# injection-feedforward.net
KiCad netlist of a schematic drawn in EAGLE
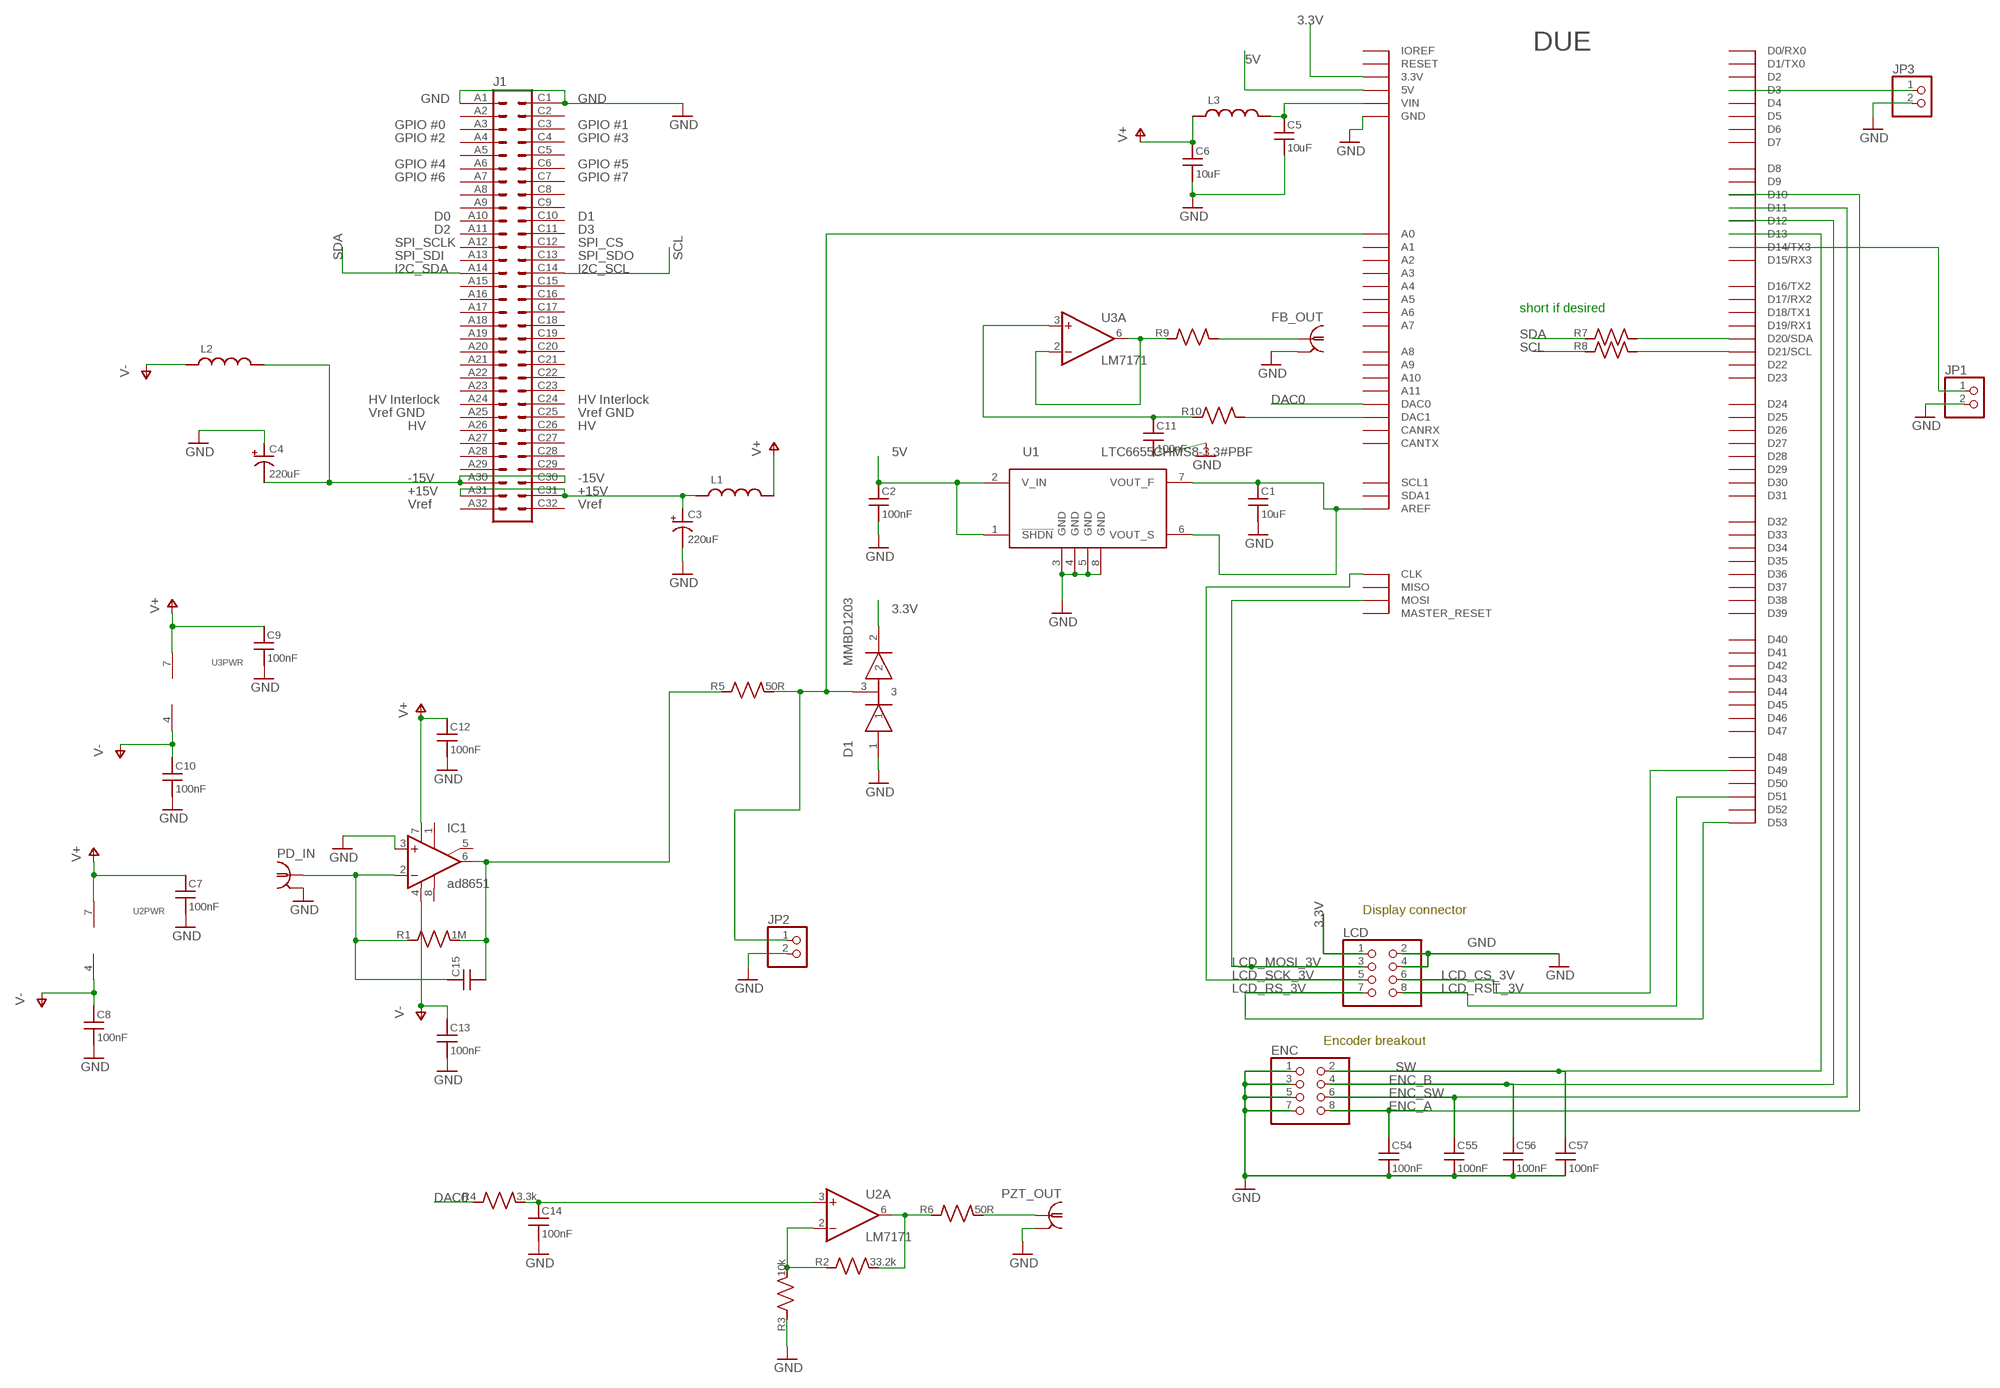
[diagram p0: schematic, sheet 1]

(export (version "E")
  (design (tool "Eeschema 10.0.6"))
  (components
    (comp (ref "C1")
      (value "10uF")
      (footprint "eagle-import:C_MLCC_0805")
      (libsource (lib "eagle-import") (part "C_MLCC_SMDCMLCC_0805"))
    )
    (comp (ref "C2")
      (value "100nF")
      (footprint "eagle-import:C_MLCC_0603")
      (libsource (lib "eagle-import") (part "C_MLCC_SMDCMLCC_0603"))
    )
    (comp (ref "C3")
      (value "220uF")
      (footprint "eagle-import:PANASONIC_F")
      (libsource (lib "eagle-import") (part "C_POL_SMDF"))
    )
    (comp (ref "C4")
      (value "220uF")
      (footprint "eagle-import:PANASONIC_F")
      (libsource (lib "eagle-import") (part "C_POL_SMDF"))
    )
    (comp (ref "C5")
      (value "10uF")
      (footprint "eagle-import:C_MLCC_0805")
      (libsource (lib "eagle-import") (part "C_MLCC_SMDCMLCC_0805"))
    )
    (comp (ref "C6")
      (value "10uF")
      (footprint "eagle-import:C_MLCC_0805")
      (libsource (lib "eagle-import") (part "C_MLCC_SMDCMLCC_0805"))
    )
    (comp (ref "C7")
      (value "100nF")
      (footprint "eagle-import:C_MLCC_0603")
      (libsource (lib "eagle-import") (part "C_MLCC_SMDCMLCC_0603"))
    )
    (comp (ref "C8")
      (value "100nF")
      (footprint "eagle-import:C_MLCC_0603")
      (libsource (lib "eagle-import") (part "C_MLCC_SMDCMLCC_0603"))
    )
    (comp (ref "C9")
      (value "100nF")
      (footprint "eagle-import:C_MLCC_0603")
      (libsource (lib "eagle-import") (part "C_MLCC_SMDCMLCC_0603"))
    )
    (comp (ref "C10")
      (value "100nF")
      (footprint "eagle-import:C_MLCC_0603")
      (libsource (lib "eagle-import") (part "C_MLCC_SMDCMLCC_0603"))
    )
    (comp (ref "C11")
      (value "100nF")
      (footprint "eagle-import:C_MLCC_0603")
      (libsource (lib "eagle-import") (part "C_MLCC_SMDCMLCC_0603"))
    )
    (comp (ref "C12")
      (value "100nF")
      (footprint "eagle-import:C_MLCC_0603")
      (libsource (lib "eagle-import") (part "C_MLCC_SMDCMLCC_0603"))
    )
    (comp (ref "C13")
      (value "100nF")
      (footprint "eagle-import:C_MLCC_0603")
      (libsource (lib "eagle-import") (part "C_MLCC_SMDCMLCC_0603"))
    )
    (comp (ref "C14")
      (value "100nF")
      (footprint "eagle-import:C_MLCC_0603")
      (libsource (lib "eagle-import") (part "C_MLCC_SMDCMLCC_0603"))
    )
    (comp (ref "C15")
      (value "C_MLCC_SMDCMLCC_0603")
      (footprint "eagle-import:C_MLCC_0603")
      (libsource (lib "eagle-import") (part "C_MLCC_SMDCMLCC_0603"))
    )
    (comp (ref "C54")
      (value "100nF")
      (footprint "eagle-import:C_MLCC_0603")
      (fields (field (name "PARTNO") "1276-1936-1-ND"))
      (libsource (lib "eagle-import") (part "C_MLCC_SMDCMLCC_0603"))
    )
    (comp (ref "C55")
      (value "100nF")
      (footprint "eagle-import:C_MLCC_0603")
      (fields (field (name "PARTNO") "1276-1936-1-ND"))
      (libsource (lib "eagle-import") (part "C_MLCC_SMDCMLCC_0603"))
    )
    (comp (ref "C56")
      (value "100nF")
      (footprint "eagle-import:C_MLCC_0603")
      (fields (field (name "PARTNO") "1276-1936-1-ND"))
      (libsource (lib "eagle-import") (part "C_MLCC_SMDCMLCC_0603"))
    )
    (comp (ref "C57")
      (value "100nF")
      (footprint "eagle-import:C_MLCC_0603")
      (fields (field (name "PARTNO") "1276-1936-1-ND"))
      (libsource (lib "eagle-import") (part "C_MLCC_SMDCMLCC_0603"))
    )
    (comp (ref "D1")
      (value "MMBD1203")
      (footprint "eagle-import:SOT23")
      (libsource (lib "eagle-import") (part "MMBD1203"))
    )
    (comp (ref "ENC")
      (value "PINHD-2X4-SHROUD")
      (footprint "eagle-import:ML08")
      (fields (field (name "PARTNO") "609-3530-ND"))
      (libsource (lib "eagle-import") (part "PINHD-2X4-SHROUD"))
    )
    (comp (ref "FB_OUT")
      (value "BNC-H")
      (footprint "eagle-import:BNC90")
      (libsource (lib "eagle-import") (part "BNC-H"))
    )
    (comp (ref "IC1")
      (value "ad8651")
      (footprint "eagle-import:SO08")
      (libsource (lib "eagle-import") (part "OPAMP-SO"))
    )
    (comp (ref "J1")
      (value "VG64C")
      (footprint "eagle-import:VG64-CUTOUT")
      (libsource (lib "eagle-import") (part "VG64C"))
    )
    (comp (ref "JP1")
      (value "PINHD-1X2")
      (footprint "eagle-import:1X02")
      (libsource (lib "eagle-import") (part "PINHD-1X2"))
    )
    (comp (ref "JP2")
      (value "PINHD-1X2")
      (footprint "eagle-import:1X02")
      (libsource (lib "eagle-import") (part "PINHD-1X2"))
    )
    (comp (ref "JP3")
      (value "PINHD-1X2")
      (footprint "eagle-import:1X02")
      (libsource (lib "eagle-import") (part "PINHD-1X2"))
    )
    (comp (ref "L1")
      (value "L_FERRITE_SMDLFERRITE_0603")
      (footprint "eagle-import:L_FERRITE_0603")
      (libsource (lib "eagle-import") (part "L_FERRITE_SMDLFERRITE_0603"))
    )
    (comp (ref "L2")
      (value "L_FERRITE_SMDLFERRITE_0603")
      (footprint "eagle-import:L_FERRITE_0603")
      (libsource (lib "eagle-import") (part "L_FERRITE_SMDLFERRITE_0603"))
    )
    (comp (ref "L3")
      (value "L_FERRITE_SMDLFERRITE_0603")
      (footprint "eagle-import:L_FERRITE_0603")
      (libsource (lib "eagle-import") (part "L_FERRITE_SMDLFERRITE_0603"))
    )
    (comp (ref "LCD")
      (value "PINHD-2X4-SHROUD")
      (footprint "eagle-import:ML08")
      (fields (field (name "PARTNO") "609-3530-ND"))
      (libsource (lib "eagle-import") (part "PINHD-2X4-SHROUD"))
    )
    (comp (ref "PD_IN")
      (value "BNC-H")
      (footprint "eagle-import:BNC90")
      (libsource (lib "eagle-import") (part "BNC-H"))
    )
    (comp (ref "PZT_OUT")
      (value "BNC-H")
      (footprint "eagle-import:BNC90")
      (libsource (lib "eagle-import") (part "BNC-H"))
    )
    (comp (ref "R1")
      (value "1M")
      (footprint "eagle-import:R_0603")
      (libsource (lib "eagle-import") (part "R_SMDR0603"))
    )
    (comp (ref "R2")
      (value "33.2k")
      (footprint "eagle-import:R_0603")
      (libsource (lib "eagle-import") (part "R_SMDR0603"))
    )
    (comp (ref "R3")
      (value "10k")
      (footprint "eagle-import:R_0603")
      (libsource (lib "eagle-import") (part "R_SMDR0603"))
    )
    (comp (ref "R4")
      (value "3.3k")
      (footprint "eagle-import:R_0603")
      (libsource (lib "eagle-import") (part "R_SMDR0603"))
    )
    (comp (ref "R5")
      (value "50R")
      (footprint "eagle-import:R_0603")
      (libsource (lib "eagle-import") (part "R_SMDR0603"))
    )
    (comp (ref "R6")
      (value "50R")
      (footprint "eagle-import:R_0603")
      (libsource (lib "eagle-import") (part "R_SMDR0603"))
    )
    (comp (ref "R7")
      (value "R_SMDR0603")
      (footprint "eagle-import:R_0603")
      (libsource (lib "eagle-import") (part "R_SMDR0603"))
    )
    (comp (ref "R8")
      (value "R_SMDR0603")
      (footprint "eagle-import:R_0603")
      (libsource (lib "eagle-import") (part "R_SMDR0603"))
    )
    (comp (ref "R9")
      (value "R_SMDR0603")
      (footprint "eagle-import:R_0603")
      (libsource (lib "eagle-import") (part "R_SMDR0603"))
    )
    (comp (ref "R10")
      (value "R_SMDR0603")
      (footprint "eagle-import:R_0603")
      (libsource (lib "eagle-import") (part "R_SMDR0603"))
    )
    (comp (ref "U$1")
      (value "DUE_SHIELD")
      (footprint "eagle-import:DUE_SHIELD")
      (libsource (lib "eagle-import") (part "DUE_SHIELD"))
    )
    (comp (ref "U1")
      (value "LTC6655CHMS8-3.3#PBF")
      (footprint "eagle-import:MSOP8")
      (libsource (lib "eagle-import") (part "LTC6655CHMS8-3.3#PBF"))
    )
    (comp (ref "U2")
      (value "LM7171")
      (footprint "eagle-import:SO08$1")
      (libsource (lib "eagle-import") (part "LM7171"))
    )
    (comp (ref "U3")
      (value "LM7171")
      (footprint "eagle-import:SO08$1")
      (libsource (lib "eagle-import") (part "LM7171"))
    )
  )
  (nets
    (net (code "1") (name "/3.3V") (class "Default")
      (node (ref "D1") (pin "2") (pinfunction "2_2") (pintype "bidirectional"))
      (node (ref "LCD") (pin "1") (pinfunction "1_1") (pintype "passive"))
      (node (ref "U$1") (pin "3.3") (pinfunction "3.3V_3.3") (pintype "bidirectional"))
    )
    (net (code "2") (name "/5V") (class "Default")
      (node (ref "C2") (pin "P$1") (pinfunction "1_P$1") (pintype "passive"))
      (node (ref "U$1") (pin "5V0") (pinfunction "5V_5V0") (pintype "bidirectional"))
      (node (ref "U$1") (pin "5V1") (pinfunction "5V_5V1") (pintype "bidirectional"))
      (node (ref "U$1") (pin "5V2") (pinfunction "5V_5V2") (pintype "bidirectional"))
      (node (ref "U$1") (pin "5V3") (pinfunction "5V_5V3") (pintype "bidirectional"))
      (node (ref "U1") (pin "1") (pinfunction "~{SHDN}_1") (pintype "bidirectional"))
      (node (ref "U1") (pin "2") (pinfunction "V_IN_2") (pintype "bidirectional"))
    )
    (net (code "3") (name "/DAC0") (class "Default")
      (node (ref "R4") (pin "P$1") (pinfunction "1_P$1") (pintype "passive"))
      (node (ref "U$1") (pin "DAC0") (pinfunction "DAC0_DAC0") (pintype "bidirectional"))
    )
    (net (code "4") (name "/ENC_A") (class "Default")
      (node (ref "C54") (pin "P$1") (pinfunction "1_P$1") (pintype "passive"))
      (node (ref "ENC") (pin "8") (pinfunction "8_8") (pintype "passive"))
      (node (ref "U$1") (pin "10") (pinfunction "D10_10") (pintype "bidirectional"))
    )
    (net (code "5") (name "/ENC_B") (class "Default")
      (node (ref "C56") (pin "P$1") (pinfunction "1_P$1") (pintype "passive"))
      (node (ref "ENC") (pin "4") (pinfunction "4_4") (pintype "passive"))
      (node (ref "U$1") (pin "12") (pinfunction "D12_12") (pintype "bidirectional"))
    )
    (net (code "6") (name "/ENC_SW") (class "Default")
      (node (ref "C55") (pin "P$1") (pinfunction "1_P$1") (pintype "passive"))
      (node (ref "ENC") (pin "6") (pinfunction "6_6") (pintype "passive"))
      (node (ref "U$1") (pin "11") (pinfunction "D11_11") (pintype "bidirectional"))
    )
    (net (code "7") (name "/LCD_CS_3V") (class "Default")
      (node (ref "LCD") (pin "6") (pinfunction "6_6") (pintype "passive"))
      (node (ref "U$1") (pin "49") (pinfunction "D49_49") (pintype "bidirectional"))
    )
    (net (code "8") (name "/LCD_MOSI_3V") (class "Default")
      (node (ref "LCD") (pin "3") (pinfunction "3_3") (pintype "passive"))
      (node (ref "U$1") (pin "MOSI") (pinfunction "MOSI_MOSI") (pintype "bidirectional"))
    )
    (net (code "9") (name "/LCD_RST_3V") (class "Default")
      (node (ref "LCD") (pin "8") (pinfunction "8_8") (pintype "passive"))
      (node (ref "U$1") (pin "51") (pinfunction "D51_51") (pintype "bidirectional"))
    )
    (net (code "10") (name "/LCD_RS_3V") (class "Default")
      (node (ref "LCD") (pin "7") (pinfunction "7_7") (pintype "passive"))
      (node (ref "U$1") (pin "53") (pinfunction "D53_53") (pintype "bidirectional"))
    )
    (net (code "11") (name "/LCD_SCK_3V") (class "Default")
      (node (ref "LCD") (pin "5") (pinfunction "5_5") (pintype "passive"))
      (node (ref "U$1") (pin "CLK") (pinfunction "CLK_CLK") (pintype "bidirectional"))
    )
    (net (code "12") (name "/SCL") (class "Default")
      (node (ref "J1") (pin "C14") (pinfunction "C14_C14") (pintype "passive"))
      (node (ref "R8") (pin "P$1") (pinfunction "1_P$1") (pintype "passive"))
    )
    (net (code "13") (name "/SDA") (class "Default")
      (node (ref "J1") (pin "A14") (pinfunction "A14_A14") (pintype "passive"))
      (node (ref "R7") (pin "P$1") (pinfunction "1_P$1") (pintype "passive"))
    )
    (net (code "14") (name "/SW") (class "Default")
      (node (ref "C57") (pin "P$1") (pinfunction "1_P$1") (pintype "passive"))
      (node (ref "ENC") (pin "2") (pinfunction "2_2") (pintype "passive"))
      (node (ref "U$1") (pin "13") (pinfunction "D13_13") (pintype "bidirectional"))
    )
    (net (code "15") (name "GND") (class "Default")
      (node (ref "C1") (pin "P$2") (pinfunction "2_P$2") (pintype "passive"))
      (node (ref "C10") (pin "P$2") (pinfunction "2_P$2") (pintype "passive"))
      (node (ref "C11") (pin "P$2") (pinfunction "2_P$2") (pintype "passive"))
      (node (ref "C12") (pin "P$2") (pinfunction "2_P$2") (pintype "passive"))
      (node (ref "C13") (pin "P$2") (pinfunction "2_P$2") (pintype "passive"))
      (node (ref "C14") (pin "P$2") (pinfunction "2_P$2") (pintype "passive"))
      (node (ref "C2") (pin "P$2") (pinfunction "2_P$2") (pintype "passive"))
      (node (ref "C3") (pin "-") (pinfunction "-_-") (pintype "passive"))
      (node (ref "C4") (pin "+") (pinfunction "+_+") (pintype "passive"))
      (node (ref "C5") (pin "P$2") (pinfunction "2_P$2") (pintype "passive"))
      (node (ref "C54") (pin "P$2") (pinfunction "2_P$2") (pintype "passive"))
      (node (ref "C55") (pin "P$2") (pinfunction "2_P$2") (pintype "passive"))
      (node (ref "C56") (pin "P$2") (pinfunction "2_P$2") (pintype "passive"))
      (node (ref "C57") (pin "P$2") (pinfunction "2_P$2") (pintype "passive"))
      (node (ref "C6") (pin "P$2") (pinfunction "2_P$2") (pintype "passive"))
      (node (ref "C7") (pin "P$2") (pinfunction "2_P$2") (pintype "passive"))
      (node (ref "C8") (pin "P$2") (pinfunction "2_P$2") (pintype "passive"))
      (node (ref "C9") (pin "P$2") (pinfunction "2_P$2") (pintype "passive"))
      (node (ref "D1") (pin "1") (pinfunction "1_1") (pintype "bidirectional"))
      (node (ref "ENC") (pin "1") (pinfunction "1_1") (pintype "passive"))
      (node (ref "ENC") (pin "3") (pinfunction "3_3") (pintype "passive"))
      (node (ref "ENC") (pin "5") (pinfunction "5_5") (pintype "passive"))
      (node (ref "ENC") (pin "7") (pinfunction "7_7") (pintype "passive"))
      (node (ref "FB_OUT") (pin "2") (pinfunction "2_2") (pintype "passive"))
      (node (ref "IC1") (pin "3") (pinfunction "+IN_3") (pintype "input"))
      (node (ref "J1") (pin "A1") (pinfunction "A1_A1") (pintype "passive"))
      (node (ref "J1") (pin "C1") (pinfunction "C1_C1") (pintype "passive"))
      (node (ref "JP1") (pin "2") (pinfunction "2_2") (pintype "passive"))
      (node (ref "JP2") (pin "2") (pinfunction "2_2") (pintype "passive"))
      (node (ref "JP3") (pin "2") (pinfunction "2_2") (pintype "passive"))
      (node (ref "LCD") (pin "2") (pinfunction "2_2") (pintype "passive"))
      (node (ref "LCD") (pin "4") (pinfunction "4_4") (pintype "passive"))
      (node (ref "PD_IN") (pin "2") (pinfunction "2_2") (pintype "passive"))
      (node (ref "PZT_OUT") (pin "2") (pinfunction "2_2") (pintype "passive"))
      (node (ref "R3") (pin "P$1") (pinfunction "1_P$1") (pintype "passive"))
      (node (ref "U$1") (pin "GND") (pinfunction "GND_GND") (pintype "bidirectional"))
      (node (ref "U$1") (pin "GND0") (pinfunction "GND_GND0") (pintype "bidirectional"))
      (node (ref "U$1") (pin "GND1") (pinfunction "GND_GND1") (pintype "bidirectional"))
      (node (ref "U$1") (pin "GND2") (pinfunction "GND_GND2") (pintype "bidirectional"))
      (node (ref "U$1") (pin "GND3") (pinfunction "GND_GND3") (pintype "bidirectional"))
      (node (ref "U$1") (pin "GND4") (pinfunction "GND_GND4") (pintype "bidirectional"))
      (node (ref "U1") (pin "3") (pinfunction "GND_3") (pintype "bidirectional"))
      (node (ref "U1") (pin "4") (pinfunction "GND_4") (pintype "bidirectional"))
      (node (ref "U1") (pin "5") (pinfunction "GND_5") (pintype "bidirectional"))
      (node (ref "U1") (pin "8") (pinfunction "GND_8") (pintype "bidirectional"))
    )
    (net (code "16") (name "Net-(C1-1)") (class "Default")
      (node (ref "C1") (pin "P$1") (pinfunction "1_P$1") (pintype "passive"))
      (node (ref "U$1") (pin "AREF") (pinfunction "AREF_AREF") (pintype "bidirectional"))
      (node (ref "U1") (pin "6") (pinfunction "VOUT_S_6") (pintype "bidirectional"))
      (node (ref "U1") (pin "7") (pinfunction "VOUT_F_7") (pintype "bidirectional"))
    )
    (net (code "17") (name "Net-(C5-1)") (class "Default")
      (node (ref "C5") (pin "P$1") (pinfunction "1_P$1") (pintype "passive"))
      (node (ref "L3") (pin "P$2") (pinfunction "2_P$2") (pintype "passive"))
      (node (ref "U$1") (pin "VIN") (pinfunction "VIN_VIN") (pintype "bidirectional"))
    )
    (net (code "18") (name "Net-(C11-1)") (class "Default")
      (node (ref "C11") (pin "P$1") (pinfunction "1_P$1") (pintype "passive"))
      (node (ref "R10") (pin "P$1") (pinfunction "1_P$1") (pintype "passive"))
      (node (ref "U3") (pin "3") (pinfunction "+IN_3") (pintype "input"))
    )
    (net (code "19") (name "Net-(C14-1)") (class "Default")
      (node (ref "C14") (pin "P$1") (pinfunction "1_P$1") (pintype "passive"))
      (node (ref "R4") (pin "P$2") (pinfunction "2_P$2") (pintype "passive"))
      (node (ref "U2") (pin "3") (pinfunction "+IN_3") (pintype "input"))
    )
    (net (code "20") (name "Net-(C15-1)") (class "Default")
      (node (ref "C15") (pin "P$1") (pinfunction "1_P$1") (pintype "passive"))
      (node (ref "IC1") (pin "2") (pinfunction "-IN_2") (pintype "input"))
      (node (ref "PD_IN") (pin "1") (pinfunction "1_1") (pintype "passive"))
      (node (ref "R1") (pin "P$1") (pinfunction "1_P$1") (pintype "passive"))
    )
    (net (code "21") (name "Net-(C15-2)") (class "Default")
      (node (ref "C15") (pin "P$2") (pinfunction "2_P$2") (pintype "passive"))
      (node (ref "IC1") (pin "6") (pinfunction "OUT_6") (pintype "output"))
      (node (ref "R1") (pin "P$2") (pinfunction "2_P$2") (pintype "passive"))
      (node (ref "R5") (pin "P$1") (pinfunction "1_P$1") (pintype "passive"))
    )
    (net (code "22") (name "Net-(L1-1)") (class "Default")
      (node (ref "C3") (pin "+") (pinfunction "+_+") (pintype "passive"))
      (node (ref "J1") (pin "A31") (pinfunction "A31_A31") (pintype "passive"))
      (node (ref "J1") (pin "C31") (pinfunction "C31_C31") (pintype "passive"))
      (node (ref "L1") (pin "P$1") (pinfunction "1_P$1") (pintype "passive"))
    )
    (net (code "23") (name "Net-(L2-2)") (class "Default")
      (node (ref "C4") (pin "-") (pinfunction "-_-") (pintype "passive"))
      (node (ref "J1") (pin "A30") (pinfunction "A30_A30") (pintype "passive"))
      (node (ref "J1") (pin "C30") (pinfunction "C30_C30") (pintype "passive"))
      (node (ref "L2") (pin "P$2") (pinfunction "2_P$2") (pintype "passive"))
    )
    (net (code "24") (name "Net-(R2-1)") (class "Default")
      (node (ref "R2") (pin "P$1") (pinfunction "1_P$1") (pintype "passive"))
      (node (ref "R3") (pin "P$2") (pinfunction "2_P$2") (pintype "passive"))
      (node (ref "U2") (pin "2") (pinfunction "-IN_2") (pintype "input"))
    )
    (net (code "25") (name "Net-(R2-2)") (class "Default")
      (node (ref "R2") (pin "P$2") (pinfunction "2_P$2") (pintype "passive"))
      (node (ref "R6") (pin "P$1") (pinfunction "1_P$1") (pintype "passive"))
      (node (ref "U2") (pin "6") (pinfunction "OUT_6") (pintype "output"))
    )
    (net (code "26") (name "Net-(R5-2)") (class "Default")
      (node (ref "D1") (pin "3") (pinfunction "3_3") (pintype "bidirectional"))
      (node (ref "JP2") (pin "1") (pinfunction "1_1") (pintype "passive"))
      (node (ref "R5") (pin "P$2") (pinfunction "2_P$2") (pintype "passive"))
      (node (ref "U$1") (pin "A0") (pinfunction "A0_A0") (pintype "bidirectional"))
    )
    (net (code "27") (name "Net-(R6-2)") (class "Default")
      (node (ref "PZT_OUT") (pin "1") (pinfunction "1_1") (pintype "passive"))
      (node (ref "R6") (pin "P$2") (pinfunction "2_P$2") (pintype "passive"))
    )
    (net (code "28") (name "Net-(R7-2)") (class "Default")
      (node (ref "R7") (pin "P$2") (pinfunction "2_P$2") (pintype "passive"))
      (node (ref "U$1") (pin "20") (pinfunction "D20/SDA_20") (pintype "bidirectional"))
    )
    (net (code "29") (name "Net-(R8-2)") (class "Default")
      (node (ref "R8") (pin "P$2") (pinfunction "2_P$2") (pintype "passive"))
      (node (ref "U$1") (pin "21") (pinfunction "D21/SCL_21") (pintype "bidirectional"))
    )
    (net (code "30") (name "Net-(R9-1)") (class "Default")
      (node (ref "R9") (pin "P$1") (pinfunction "1_P$1") (pintype "passive"))
      (node (ref "U3") (pin "2") (pinfunction "-IN_2") (pintype "input"))
      (node (ref "U3") (pin "6") (pinfunction "OUT_6") (pintype "output"))
    )
    (net (code "31") (name "Net-(R9-2)") (class "Default")
      (node (ref "FB_OUT") (pin "1") (pinfunction "1_1") (pintype "passive"))
      (node (ref "R9") (pin "P$2") (pinfunction "2_P$2") (pintype "passive"))
    )
    (net (code "32") (name "Net-(R10-2)") (class "Default")
      (node (ref "R10") (pin "P$2") (pinfunction "2_P$2") (pintype "passive"))
      (node (ref "U$1") (pin "DAC1") (pinfunction "DAC1_DAC1") (pintype "bidirectional"))
    )
    (net (code "33") (name "Net-(U$1-D3)") (class "Default")
      (node (ref "JP3") (pin "1") (pinfunction "1_1") (pintype "passive"))
      (node (ref "U$1") (pin "3") (pinfunction "D3_3") (pintype "bidirectional"))
    )
    (net (code "34") (name "Net-(U$1-D14{slash}TX3)") (class "Default")
      (node (ref "JP1") (pin "1") (pinfunction "1_1") (pintype "passive"))
      (node (ref "U$1") (pin "14") (pinfunction "D14/TX3_14") (pintype "bidirectional"))
    )
    (net (code "35") (name "V+") (class "Default")
      (node (ref "C12") (pin "P$1") (pinfunction "1_P$1") (pintype "passive"))
      (node (ref "C6") (pin "P$1") (pinfunction "1_P$1") (pintype "passive"))
      (node (ref "C7") (pin "P$1") (pinfunction "1_P$1") (pintype "passive"))
      (node (ref "C9") (pin "P$1") (pinfunction "1_P$1") (pintype "passive"))
      (node (ref "IC1") (pin "7") (pinfunction "V+_7") (pintype "power_in"))
      (node (ref "L1") (pin "P$2") (pinfunction "2_P$2") (pintype "passive"))
      (node (ref "L3") (pin "P$1") (pinfunction "1_P$1") (pintype "passive"))
      (node (ref "U2") (pin "7") (pinfunction "V+_7") (pintype "power_in"))
      (node (ref "U3") (pin "7") (pinfunction "V+_7") (pintype "power_in"))
    )
    (net (code "36") (name "V-") (class "Default")
      (node (ref "C10") (pin "P$1") (pinfunction "1_P$1") (pintype "passive"))
      (node (ref "C13") (pin "P$1") (pinfunction "1_P$1") (pintype "passive"))
      (node (ref "C8") (pin "P$1") (pinfunction "1_P$1") (pintype "passive"))
      (node (ref "IC1") (pin "4") (pinfunction "V-_4") (pintype "power_in"))
      (node (ref "L2") (pin "P$1") (pinfunction "1_P$1") (pintype "passive"))
      (node (ref "U2") (pin "4") (pinfunction "V-_4") (pintype "power_in"))
      (node (ref "U3") (pin "4") (pinfunction "V-_4") (pintype "power_in"))
    )
    (net (code "37") (name "unconnected-(IC1-ON1-Pad1)") (class "Default")
      (node (ref "IC1") (pin "1") (pinfunction "ON1_1") (pintype "passive"))
    )
    (net (code "38") (name "unconnected-(IC1-ON2-Pad5)") (class "Default")
      (node (ref "IC1") (pin "5") (pinfunction "ON2_5") (pintype "passive"))
    )
    (net (code "39") (name "unconnected-(IC1-OPT-Pad8)") (class "Default")
      (node (ref "IC1") (pin "8") (pinfunction "OPT_8") (pintype "passive"))
    )
    (net (code "40") (name "unconnected-(J1-PadA2)") (class "Default")
      (node (ref "J1") (pin "A2") (pinfunction "A2_A2") (pintype "passive"))
    )
    (net (code "41") (name "unconnected-(J1-PadA3)") (class "Default")
      (node (ref "J1") (pin "A3") (pinfunction "A3_A3") (pintype "passive"))
    )
    (net (code "42") (name "unconnected-(J1-PadA4)") (class "Default")
      (node (ref "J1") (pin "A4") (pinfunction "A4_A4") (pintype "passive"))
    )
    (net (code "43") (name "unconnected-(J1-PadA5)") (class "Default")
      (node (ref "J1") (pin "A5") (pinfunction "A5_A5") (pintype "passive"))
    )
    (net (code "44") (name "unconnected-(J1-PadA6)") (class "Default")
      (node (ref "J1") (pin "A6") (pinfunction "A6_A6") (pintype "passive"))
    )
    (net (code "45") (name "unconnected-(J1-PadA7)") (class "Default")
      (node (ref "J1") (pin "A7") (pinfunction "A7_A7") (pintype "passive"))
    )
    (net (code "46") (name "unconnected-(J1-PadA8)") (class "Default")
      (node (ref "J1") (pin "A8") (pinfunction "A8_A8") (pintype "passive"))
    )
    (net (code "47") (name "unconnected-(J1-PadA9)") (class "Default")
      (node (ref "J1") (pin "A9") (pinfunction "A9_A9") (pintype "passive"))
    )
    (net (code "48") (name "unconnected-(J1-PadA10)") (class "Default")
      (node (ref "J1") (pin "A10") (pinfunction "A10_A10") (pintype "passive"))
    )
    (net (code "49") (name "unconnected-(J1-PadA11)") (class "Default")
      (node (ref "J1") (pin "A11") (pinfunction "A11_A11") (pintype "passive"))
    )
    (net (code "50") (name "unconnected-(J1-PadA12)") (class "Default")
      (node (ref "J1") (pin "A12") (pinfunction "A12_A12") (pintype "passive"))
    )
    (net (code "51") (name "unconnected-(J1-PadA13)") (class "Default")
      (node (ref "J1") (pin "A13") (pinfunction "A13_A13") (pintype "passive"))
    )
    (net (code "52") (name "unconnected-(J1-PadA15)") (class "Default")
      (node (ref "J1") (pin "A15") (pinfunction "A15_A15") (pintype "passive"))
    )
    (net (code "53") (name "unconnected-(J1-PadA16)") (class "Default")
      (node (ref "J1") (pin "A16") (pinfunction "A16_A16") (pintype "passive"))
    )
    (net (code "54") (name "unconnected-(J1-PadA17)") (class "Default")
      (node (ref "J1") (pin "A17") (pinfunction "A17_A17") (pintype "passive"))
    )
    (net (code "55") (name "unconnected-(J1-PadA18)") (class "Default")
      (node (ref "J1") (pin "A18") (pinfunction "A18_A18") (pintype "passive"))
    )
    (net (code "56") (name "unconnected-(J1-PadA19)") (class "Default")
      (node (ref "J1") (pin "A19") (pinfunction "A19_A19") (pintype "passive"))
    )
    (net (code "57") (name "unconnected-(J1-PadA20)") (class "Default")
      (node (ref "J1") (pin "A20") (pinfunction "A20_A20") (pintype "passive"))
    )
    (net (code "58") (name "unconnected-(J1-PadA21)") (class "Default")
      (node (ref "J1") (pin "A21") (pinfunction "A21_A21") (pintype "passive"))
    )
    (net (code "59") (name "unconnected-(J1-PadA22)") (class "Default")
      (node (ref "J1") (pin "A22") (pinfunction "A22_A22") (pintype "passive"))
    )
    (net (code "60") (name "unconnected-(J1-PadA23)") (class "Default")
      (node (ref "J1") (pin "A23") (pinfunction "A23_A23") (pintype "passive"))
    )
    (net (code "61") (name "unconnected-(J1-PadA24)") (class "Default")
      (node (ref "J1") (pin "A24") (pinfunction "A24_A24") (pintype "passive"))
    )
    (net (code "62") (name "unconnected-(J1-PadA25)") (class "Default")
      (node (ref "J1") (pin "A25") (pinfunction "A25_A25") (pintype "passive"))
    )
    (net (code "63") (name "unconnected-(J1-PadA26)") (class "Default")
      (node (ref "J1") (pin "A26") (pinfunction "A26_A26") (pintype "passive"))
    )
    (net (code "64") (name "unconnected-(J1-PadA27)") (class "Default")
      (node (ref "J1") (pin "A27") (pinfunction "A27_A27") (pintype "passive"))
    )
    (net (code "65") (name "unconnected-(J1-PadA28)") (class "Default")
      (node (ref "J1") (pin "A28") (pinfunction "A28_A28") (pintype "passive"))
    )
    (net (code "66") (name "unconnected-(J1-PadA29)") (class "Default")
      (node (ref "J1") (pin "A29") (pinfunction "A29_A29") (pintype "passive"))
    )
    (net (code "67") (name "unconnected-(J1-PadA32)") (class "Default")
      (node (ref "J1") (pin "A32") (pinfunction "A32_A32") (pintype "passive"))
    )
    (net (code "68") (name "unconnected-(J1-PadC2)") (class "Default")
      (node (ref "J1") (pin "C2") (pinfunction "C2_C2") (pintype "passive"))
    )
    (net (code "69") (name "unconnected-(J1-PadC3)") (class "Default")
      (node (ref "J1") (pin "C3") (pinfunction "C3_C3") (pintype "passive"))
    )
    (net (code "70") (name "unconnected-(J1-PadC4)") (class "Default")
      (node (ref "J1") (pin "C4") (pinfunction "C4_C4") (pintype "passive"))
    )
    (net (code "71") (name "unconnected-(J1-PadC5)") (class "Default")
      (node (ref "J1") (pin "C5") (pinfunction "C5_C5") (pintype "passive"))
    )
    (net (code "72") (name "unconnected-(J1-PadC6)") (class "Default")
      (node (ref "J1") (pin "C6") (pinfunction "C6_C6") (pintype "passive"))
    )
    (net (code "73") (name "unconnected-(J1-PadC7)") (class "Default")
      (node (ref "J1") (pin "C7") (pinfunction "C7_C7") (pintype "passive"))
    )
    (net (code "74") (name "unconnected-(J1-PadC8)") (class "Default")
      (node (ref "J1") (pin "C8") (pinfunction "C8_C8") (pintype "passive"))
    )
    (net (code "75") (name "unconnected-(J1-PadC9)") (class "Default")
      (node (ref "J1") (pin "C9") (pinfunction "C9_C9") (pintype "passive"))
    )
    (net (code "76") (name "unconnected-(J1-PadC10)") (class "Default")
      (node (ref "J1") (pin "C10") (pinfunction "C10_C10") (pintype "passive"))
    )
    (net (code "77") (name "unconnected-(J1-PadC11)") (class "Default")
      (node (ref "J1") (pin "C11") (pinfunction "C11_C11") (pintype "passive"))
    )
    (net (code "78") (name "unconnected-(J1-PadC12)") (class "Default")
      (node (ref "J1") (pin "C12") (pinfunction "C12_C12") (pintype "passive"))
    )
    (net (code "79") (name "unconnected-(J1-PadC13)") (class "Default")
      (node (ref "J1") (pin "C13") (pinfunction "C13_C13") (pintype "passive"))
    )
    (net (code "80") (name "unconnected-(J1-PadC15)") (class "Default")
      (node (ref "J1") (pin "C15") (pinfunction "C15_C15") (pintype "passive"))
    )
    (net (code "81") (name "unconnected-(J1-PadC16)") (class "Default")
      (node (ref "J1") (pin "C16") (pinfunction "C16_C16") (pintype "passive"))
    )
    (net (code "82") (name "unconnected-(J1-PadC17)") (class "Default")
      (node (ref "J1") (pin "C17") (pinfunction "C17_C17") (pintype "passive"))
    )
    (net (code "83") (name "unconnected-(J1-PadC18)") (class "Default")
      (node (ref "J1") (pin "C18") (pinfunction "C18_C18") (pintype "passive"))
    )
    (net (code "84") (name "unconnected-(J1-PadC19)") (class "Default")
      (node (ref "J1") (pin "C19") (pinfunction "C19_C19") (pintype "passive"))
    )
    (net (code "85") (name "unconnected-(J1-PadC20)") (class "Default")
      (node (ref "J1") (pin "C20") (pinfunction "C20_C20") (pintype "passive"))
    )
    (net (code "86") (name "unconnected-(J1-PadC21)") (class "Default")
      (node (ref "J1") (pin "C21") (pinfunction "C21_C21") (pintype "passive"))
    )
    (net (code "87") (name "unconnected-(J1-PadC22)") (class "Default")
      (node (ref "J1") (pin "C22") (pinfunction "C22_C22") (pintype "passive"))
    )
    (net (code "88") (name "unconnected-(J1-PadC23)") (class "Default")
      (node (ref "J1") (pin "C23") (pinfunction "C23_C23") (pintype "passive"))
    )
    (net (code "89") (name "unconnected-(J1-PadC24)") (class "Default")
      (node (ref "J1") (pin "C24") (pinfunction "C24_C24") (pintype "passive"))
    )
    (net (code "90") (name "unconnected-(J1-PadC25)") (class "Default")
      (node (ref "J1") (pin "C25") (pinfunction "C25_C25") (pintype "passive"))
    )
    (net (code "91") (name "unconnected-(J1-PadC26)") (class "Default")
      (node (ref "J1") (pin "C26") (pinfunction "C26_C26") (pintype "passive"))
    )
    (net (code "92") (name "unconnected-(J1-PadC27)") (class "Default")
      (node (ref "J1") (pin "C27") (pinfunction "C27_C27") (pintype "passive"))
    )
    (net (code "93") (name "unconnected-(J1-PadC28)") (class "Default")
      (node (ref "J1") (pin "C28") (pinfunction "C28_C28") (pintype "passive"))
    )
    (net (code "94") (name "unconnected-(J1-PadC29)") (class "Default")
      (node (ref "J1") (pin "C29") (pinfunction "C29_C29") (pintype "passive"))
    )
    (net (code "95") (name "unconnected-(J1-PadC32)") (class "Default")
      (node (ref "J1") (pin "C32") (pinfunction "C32_C32") (pintype "passive"))
    )
    (net (code "96") (name "unconnected-(U$1-D0{slash}RX0-Pad0)") (class "Default")
      (node (ref "U$1") (pin "0") (pinfunction "D0/RX0_0") (pintype "bidirectional"))
    )
    (net (code "97") (name "unconnected-(U$1-D1{slash}TX0-Pad1)") (class "Default")
      (node (ref "U$1") (pin "1") (pinfunction "D1/TX0_1") (pintype "bidirectional"))
    )
    (net (code "98") (name "unconnected-(U$1-D2-Pad2)") (class "Default")
      (node (ref "U$1") (pin "2") (pinfunction "D2_2") (pintype "bidirectional"))
    )
    (net (code "99") (name "unconnected-(U$1-D4-Pad4)") (class "Default")
      (node (ref "U$1") (pin "4") (pinfunction "D4_4") (pintype "bidirectional"))
    )
    (net (code "100") (name "unconnected-(U$1-D5-Pad5)") (class "Default")
      (node (ref "U$1") (pin "5") (pinfunction "D5_5") (pintype "bidirectional"))
    )
    (net (code "101") (name "unconnected-(U$1-D6-Pad6)") (class "Default")
      (node (ref "U$1") (pin "6") (pinfunction "D6_6") (pintype "bidirectional"))
    )
    (net (code "102") (name "unconnected-(U$1-D7-Pad7)") (class "Default")
      (node (ref "U$1") (pin "7") (pinfunction "D7_7") (pintype "bidirectional"))
    )
    (net (code "103") (name "unconnected-(U$1-D8-Pad8)") (class "Default")
      (node (ref "U$1") (pin "8") (pinfunction "D8_8") (pintype "bidirectional"))
    )
    (net (code "104") (name "unconnected-(U$1-D9-Pad9)") (class "Default")
      (node (ref "U$1") (pin "9") (pinfunction "D9_9") (pintype "bidirectional"))
    )
    (net (code "105") (name "unconnected-(U$1-D15{slash}RX3-Pad15)") (class "Default")
      (node (ref "U$1") (pin "15") (pinfunction "D15/RX3_15") (pintype "bidirectional"))
    )
    (net (code "106") (name "unconnected-(U$1-D16{slash}TX2-Pad16)") (class "Default")
      (node (ref "U$1") (pin "16") (pinfunction "D16/TX2_16") (pintype "bidirectional"))
    )
    (net (code "107") (name "unconnected-(U$1-D17{slash}RX2-Pad17)") (class "Default")
      (node (ref "U$1") (pin "17") (pinfunction "D17/RX2_17") (pintype "bidirectional"))
    )
    (net (code "108") (name "unconnected-(U$1-D18{slash}TX1-Pad18)") (class "Default")
      (node (ref "U$1") (pin "18") (pinfunction "D18/TX1_18") (pintype "bidirectional"))
    )
    (net (code "109") (name "unconnected-(U$1-D19{slash}RX1-Pad19)") (class "Default")
      (node (ref "U$1") (pin "19") (pinfunction "D19/RX1_19") (pintype "bidirectional"))
    )
    (net (code "110") (name "unconnected-(U$1-D22-Pad22)") (class "Default")
      (node (ref "U$1") (pin "22") (pinfunction "D22_22") (pintype "bidirectional"))
    )
    (net (code "111") (name "unconnected-(U$1-D23-Pad23)") (class "Default")
      (node (ref "U$1") (pin "23") (pinfunction "D23_23") (pintype "bidirectional"))
    )
    (net (code "112") (name "unconnected-(U$1-D24-Pad24)") (class "Default")
      (node (ref "U$1") (pin "24") (pinfunction "D24_24") (pintype "bidirectional"))
    )
    (net (code "113") (name "unconnected-(U$1-D25-Pad25)") (class "Default")
      (node (ref "U$1") (pin "25") (pinfunction "D25_25") (pintype "bidirectional"))
    )
    (net (code "114") (name "unconnected-(U$1-D26-Pad26)") (class "Default")
      (node (ref "U$1") (pin "26") (pinfunction "D26_26") (pintype "bidirectional"))
    )
    (net (code "115") (name "unconnected-(U$1-D27-Pad27)") (class "Default")
      (node (ref "U$1") (pin "27") (pinfunction "D27_27") (pintype "bidirectional"))
    )
    (net (code "116") (name "unconnected-(U$1-D28-Pad28)") (class "Default")
      (node (ref "U$1") (pin "28") (pinfunction "D28_28") (pintype "bidirectional"))
    )
    (net (code "117") (name "unconnected-(U$1-D29-Pad29)") (class "Default")
      (node (ref "U$1") (pin "29") (pinfunction "D29_29") (pintype "bidirectional"))
    )
    (net (code "118") (name "unconnected-(U$1-D30-Pad30)") (class "Default")
      (node (ref "U$1") (pin "30") (pinfunction "D30_30") (pintype "bidirectional"))
    )
    (net (code "119") (name "unconnected-(U$1-D31-Pad31)") (class "Default")
      (node (ref "U$1") (pin "31") (pinfunction "D31_31") (pintype "bidirectional"))
    )
    (net (code "120") (name "unconnected-(U$1-D32-Pad32)") (class "Default")
      (node (ref "U$1") (pin "32") (pinfunction "D32_32") (pintype "bidirectional"))
    )
    (net (code "121") (name "unconnected-(U$1-D33-Pad33)") (class "Default")
      (node (ref "U$1") (pin "33") (pinfunction "D33_33") (pintype "bidirectional"))
    )
    (net (code "122") (name "unconnected-(U$1-D34-Pad34)") (class "Default")
      (node (ref "U$1") (pin "34") (pinfunction "D34_34") (pintype "bidirectional"))
    )
    (net (code "123") (name "unconnected-(U$1-D35-Pad35)") (class "Default")
      (node (ref "U$1") (pin "35") (pinfunction "D35_35") (pintype "bidirectional"))
    )
    (net (code "124") (name "unconnected-(U$1-D36-Pad36)") (class "Default")
      (node (ref "U$1") (pin "36") (pinfunction "D36_36") (pintype "bidirectional"))
    )
    (net (code "125") (name "unconnected-(U$1-D37-Pad37)") (class "Default")
      (node (ref "U$1") (pin "37") (pinfunction "D37_37") (pintype "bidirectional"))
    )
    (net (code "126") (name "unconnected-(U$1-D38-Pad38)") (class "Default")
      (node (ref "U$1") (pin "38") (pinfunction "D38_38") (pintype "bidirectional"))
    )
    (net (code "127") (name "unconnected-(U$1-D39-Pad39)") (class "Default")
      (node (ref "U$1") (pin "39") (pinfunction "D39_39") (pintype "bidirectional"))
    )
    (net (code "128") (name "unconnected-(U$1-D40-Pad40)") (class "Default")
      (node (ref "U$1") (pin "40") (pinfunction "D40_40") (pintype "bidirectional"))
    )
    (net (code "129") (name "unconnected-(U$1-D41-Pad41)") (class "Default")
      (node (ref "U$1") (pin "41") (pinfunction "D41_41") (pintype "bidirectional"))
    )
    (net (code "130") (name "unconnected-(U$1-D42-Pad42)") (class "Default")
      (node (ref "U$1") (pin "42") (pinfunction "D42_42") (pintype "bidirectional"))
    )
    (net (code "131") (name "unconnected-(U$1-D43-Pad43)") (class "Default")
      (node (ref "U$1") (pin "43") (pinfunction "D43_43") (pintype "bidirectional"))
    )
    (net (code "132") (name "unconnected-(U$1-D44-Pad44)") (class "Default")
      (node (ref "U$1") (pin "44") (pinfunction "D44_44") (pintype "bidirectional"))
    )
    (net (code "133") (name "unconnected-(U$1-D45-Pad45)") (class "Default")
      (node (ref "U$1") (pin "45") (pinfunction "D45_45") (pintype "bidirectional"))
    )
    (net (code "134") (name "unconnected-(U$1-D46-Pad46)") (class "Default")
      (node (ref "U$1") (pin "46") (pinfunction "D46_46") (pintype "bidirectional"))
    )
    (net (code "135") (name "unconnected-(U$1-D47-Pad47)") (class "Default")
      (node (ref "U$1") (pin "47") (pinfunction "D47_47") (pintype "bidirectional"))
    )
    (net (code "136") (name "unconnected-(U$1-D48-Pad48)") (class "Default")
      (node (ref "U$1") (pin "48") (pinfunction "D48_48") (pintype "bidirectional"))
    )
    (net (code "137") (name "unconnected-(U$1-D50-Pad50)") (class "Default")
      (node (ref "U$1") (pin "50") (pinfunction "D50_50") (pintype "bidirectional"))
    )
    (net (code "138") (name "unconnected-(U$1-D52-Pad52)") (class "Default")
      (node (ref "U$1") (pin "52") (pinfunction "D52_52") (pintype "bidirectional"))
    )
    (net (code "139") (name "unconnected-(U$1-PadA1)") (class "Default")
      (node (ref "U$1") (pin "A1") (pinfunction "A1_A1") (pintype "bidirectional"))
    )
    (net (code "140") (name "unconnected-(U$1-PadA2)") (class "Default")
      (node (ref "U$1") (pin "A2") (pinfunction "A2_A2") (pintype "bidirectional"))
    )
    (net (code "141") (name "unconnected-(U$1-PadA3)") (class "Default")
      (node (ref "U$1") (pin "A3") (pinfunction "A3_A3") (pintype "bidirectional"))
    )
    (net (code "142") (name "unconnected-(U$1-PadA4)") (class "Default")
      (node (ref "U$1") (pin "A4") (pinfunction "A4_A4") (pintype "bidirectional"))
    )
    (net (code "143") (name "unconnected-(U$1-PadA5)") (class "Default")
      (node (ref "U$1") (pin "A5") (pinfunction "A5_A5") (pintype "bidirectional"))
    )
    (net (code "144") (name "unconnected-(U$1-PadA6)") (class "Default")
      (node (ref "U$1") (pin "A6") (pinfunction "A6_A6") (pintype "bidirectional"))
    )
    (net (code "145") (name "unconnected-(U$1-PadA7)") (class "Default")
      (node (ref "U$1") (pin "A7") (pinfunction "A7_A7") (pintype "bidirectional"))
    )
    (net (code "146") (name "unconnected-(U$1-PadA8)") (class "Default")
      (node (ref "U$1") (pin "A8") (pinfunction "A8_A8") (pintype "bidirectional"))
    )
    (net (code "147") (name "unconnected-(U$1-PadA9)") (class "Default")
      (node (ref "U$1") (pin "A9") (pinfunction "A9_A9") (pintype "bidirectional"))
    )
    (net (code "148") (name "unconnected-(U$1-PadA10)") (class "Default")
      (node (ref "U$1") (pin "A10") (pinfunction "A10_A10") (pintype "bidirectional"))
    )
    (net (code "149") (name "unconnected-(U$1-PadA11)") (class "Default")
      (node (ref "U$1") (pin "A11") (pinfunction "A11_A11") (pintype "bidirectional"))
    )
    (net (code "150") (name "unconnected-(U$1-PadCANRX)") (class "Default")
      (node (ref "U$1") (pin "CANRX") (pinfunction "CANRX_CANRX") (pintype "bidirectional"))
    )
    (net (code "151") (name "unconnected-(U$1-PadCANTX)") (class "Default")
      (node (ref "U$1") (pin "CANTX") (pinfunction "CANTX_CANTX") (pintype "bidirectional"))
    )
    (net (code "152") (name "unconnected-(U$1-PadIOREF)") (class "Default")
      (node (ref "U$1") (pin "IOREF") (pinfunction "IOREF_IOREF") (pintype "bidirectional"))
    )
    (net (code "153") (name "unconnected-(U$1-PadMASTER_RESET)") (class "Default")
      (node (ref "U$1") (pin "MASTER_RESET") (pinfunction "MASTER_RESET_MASTER_RESET") (pintype "bidirectional"))
    )
    (net (code "154") (name "unconnected-(U$1-PadMISO)") (class "Default")
      (node (ref "U$1") (pin "MISO") (pinfunction "MISO_MISO") (pintype "bidirectional"))
    )
    (net (code "155") (name "unconnected-(U$1-PadRESET)") (class "Default")
      (node (ref "U$1") (pin "RESET") (pinfunction "RESET_RESET") (pintype "bidirectional"))
    )
    (net (code "156") (name "unconnected-(U$1-PadSCL1)") (class "Default")
      (node (ref "U$1") (pin "SCL1") (pinfunction "SCL1_SCL1") (pintype "bidirectional"))
    )
    (net (code "157") (name "unconnected-(U$1-PadSDA1)") (class "Default")
      (node (ref "U$1") (pin "SDA1") (pinfunction "SDA1_SDA1") (pintype "bidirectional"))
    )
  )
)
